# rgbstripe_fft_pcb.net
KiCad netlist of a schematic drawn in EAGLE
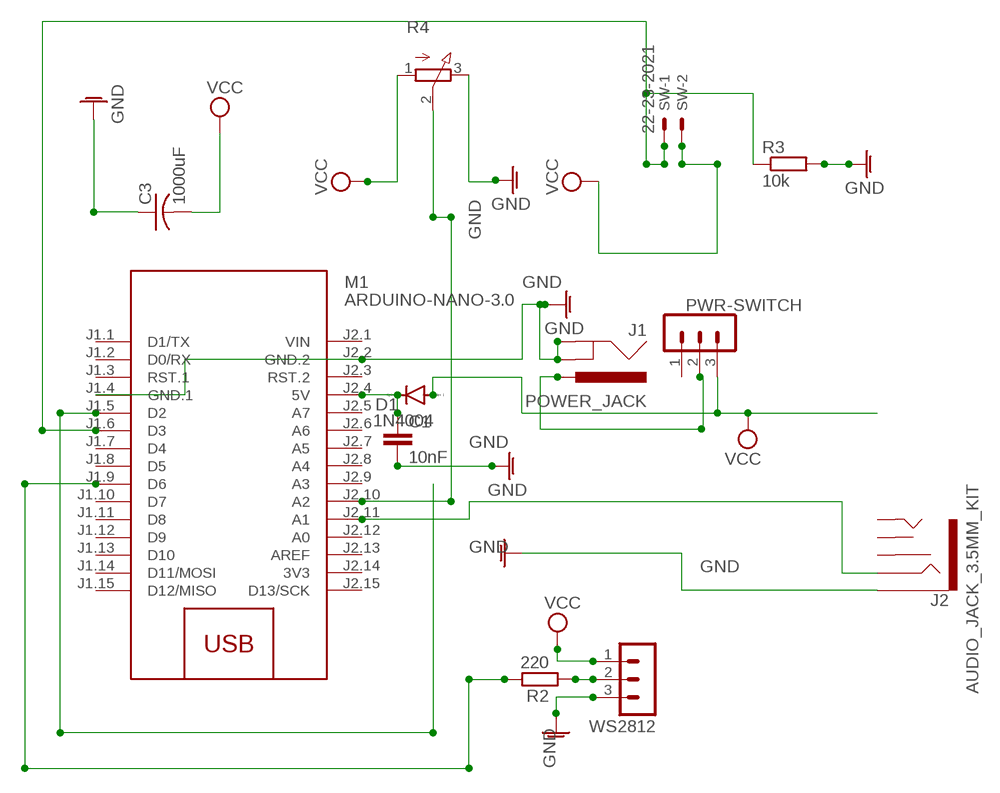
[diagram p0: schematic, sheet 1]

(export (version "E")
  (design (tool "Eeschema 10.0.6"))
  (components
    (comp (ref "C1")
      (value "10nF")
      (footprint "eagle-import:C025-025X050")
      (libsource (lib "eagle-import") (part "C-EU025-025X050"))
    )
    (comp (ref "C3")
      (value "1000uF")
      (footprint "eagle-import:C050-024X044")
      (libsource (lib "eagle-import") (part "C-US050-024X044"))
    )
    (comp (ref "D1")
      (value "1N4004")
      (footprint "eagle-import:DO41-10")
      (libsource (lib "eagle-import") (part "1N4004"))
    )
    (comp (ref "J1")
      (value "POWER_JACK")
      (footprint "eagle-import:POWER_JACK_PTH")
      (libsource (lib "eagle-import") (part "POWER_JACK"))
    )
    (comp (ref "J2")
      (value "AUDIO_JACK_3.5MM_KIT")
      (footprint "eagle-import:AUDIO-JACK-KIT")
      (libsource (lib "eagle-import") (part "AUDIO_JACK_3.5MM_KIT"))
    )
    (comp (ref "M1")
      (value "ARDUINO-NANO-3.0")
      (footprint "eagle-import:ARDUINO-NANO-3.0")
      (libsource (lib "eagle-import") (part "ARDUINO-NANO-3.0"))
    )
    (comp (ref "PWR-SWITCH")
      (value "MA03-1")
      (footprint "eagle-import:MA03-1")
      (libsource (lib "eagle-import") (part "MA03-1"))
    )
    (comp (ref "R2")
      (value "220")
      (footprint "eagle-import:0204_5")
      (libsource (lib "eagle-import") (part "R-EU_0204/5"))
    )
    (comp (ref "R3")
      (value "10k")
      (footprint "eagle-import:0204_5")
      (libsource (lib "eagle-import") (part "R-EU_0204/5"))
    )
    (comp (ref "R4")
      (value "3RP/1610N")
      (footprint "eagle-import:3RP_1610N")
      (libsource (lib "eagle-import") (part "3RP/1610N"))
    )
    (comp (ref "SW")
      (value "22-23-2021")
      (footprint "eagle-import:22-23-2021")
      (fields (field (name "MF") "MOLEX"))
      (libsource (lib "eagle-import") (part "22-23-2021"))
    )
    (comp (ref "WS2812")
      (value "MA03-1")
      (footprint "eagle-import:MA03-1")
      (libsource (lib "eagle-import") (part "MA03-1"))
    )
  )
  (nets
    (net (code "1") (name "/3V3") (class "Default")
      (node (ref "M1") (pin "J2.14") (pinfunction "3V3_J2.14") (pintype "power_in"))
    )
    (net (code "2") (name "/VIN") (class "Default")
      (node (ref "M1") (pin "J2.1") (pinfunction "VIN_J2.1") (pintype "power_in"))
    )
    (net (code "3") (name "GND") (class "Default")
      (node (ref "C1") (pin "2") (pinfunction "2_2") (pintype "passive"))
      (node (ref "C3") (pin "1") (pinfunction "1_1") (pintype "passive"))
      (node (ref "J1") (pin "GND") (pinfunction "GND_GND") (pintype "bidirectional"))
      (node (ref "J1") (pin "GNDBREAK") (pinfunction "GNDBREAK_GNDBREAK") (pintype "bidirectional"))
      (node (ref "J2") (pin "SLEEVE") (pinfunction "SLEEVE_SLEEVE") (pintype "bidirectional"))
      (node (ref "M1") (pin "J1.4") (pinfunction "GND.1_J1.4") (pintype "power_in"))
      (node (ref "M1") (pin "J2.2") (pinfunction "GND.2_J2.2") (pintype "power_in"))
      (node (ref "R3") (pin "2") (pinfunction "2_2") (pintype "passive"))
      (node (ref "R4") (pin "3") (pinfunction "E_3") (pintype "passive"))
      (node (ref "WS2812") (pin "3") (pinfunction "3_3") (pintype "passive"))
    )
    (net (code "4") (name "Net-(J1-PadPWR)") (class "Default")
      (node (ref "J1") (pin "PWR") (pinfunction "PWR_PWR") (pintype "bidirectional"))
      (node (ref "PWR-SWITCH") (pin "2") (pinfunction "2_2") (pintype "passive"))
    )
    (net (code "5") (name "Net-(M1-5V)") (class "Default")
      (node (ref "C1") (pin "1") (pinfunction "1_1") (pintype "passive"))
      (node (ref "D1") (pin "C") (pinfunction "C_C") (pintype "passive"))
      (node (ref "M1") (pin "J2.4") (pinfunction "5V_J2.4") (pintype "power_in"))
    )
    (net (code "6") (name "Net-(M1-A1)") (class "Default")
      (node (ref "J2") (pin "RING") (pinfunction "RING_RING") (pintype "bidirectional"))
      (node (ref "M1") (pin "J2.11") (pinfunction "A1_J2.11") (pintype "bidirectional"))
    )
    (net (code "7") (name "Net-(M1-A2)") (class "Default")
      (node (ref "M1") (pin "J2.10") (pinfunction "A2_J2.10") (pintype "bidirectional"))
      (node (ref "R4") (pin "2") (pinfunction "S_2") (pintype "passive"))
    )
    (net (code "8") (name "Net-(M1-D3)") (class "Default")
      (node (ref "M1") (pin "J1.6") (pinfunction "D3_J1.6") (pintype "bidirectional"))
      (node (ref "R3") (pin "1") (pinfunction "1_1") (pintype "passive"))
      (node (ref "SW") (pin "1") (pinfunction "S_1") (pintype "passive"))
    )
    (net (code "9") (name "Net-(M1-D6)") (class "Default")
      (node (ref "M1") (pin "J1.9") (pinfunction "D6_J1.9") (pintype "bidirectional"))
      (node (ref "R2") (pin "2") (pinfunction "2_2") (pintype "passive"))
    )
    (net (code "10") (name "Net-(R2-Pad1)") (class "Default")
      (node (ref "R2") (pin "1") (pinfunction "1_1") (pintype "passive"))
      (node (ref "WS2812") (pin "2") (pinfunction "2_2") (pintype "passive"))
    )
    (net (code "11") (name "VCC") (class "Default")
      (node (ref "C3") (pin "2") (pinfunction "2_2") (pintype "passive"))
      (node (ref "D1") (pin "A") (pinfunction "A_A") (pintype "passive"))
      (node (ref "PWR-SWITCH") (pin "3") (pinfunction "3_3") (pintype "passive"))
      (node (ref "R4") (pin "1") (pinfunction "A_1") (pintype "passive"))
      (node (ref "SW") (pin "2") (pinfunction "S_2") (pintype "passive"))
      (node (ref "WS2812") (pin "1") (pinfunction "1_1") (pintype "passive"))
    )
    (net (code "12") (name "unconnected-(J2-PadRSH)") (class "Default")
      (node (ref "J2") (pin "RSH") (pinfunction "RSH_RSH") (pintype "bidirectional"))
    )
    (net (code "13") (name "unconnected-(J2-PadTIP)") (class "Default")
      (node (ref "J2") (pin "TIP") (pinfunction "TIP_TIP") (pintype "bidirectional"))
    )
    (net (code "14") (name "unconnected-(J2-PadTSH)") (class "Default")
      (node (ref "J2") (pin "TSH") (pinfunction "TSH_TSH") (pintype "bidirectional"))
    )
    (net (code "15") (name "unconnected-(M1-A0-PadJ2.12)") (class "Default")
      (node (ref "M1") (pin "J2.12") (pinfunction "A0_J2.12") (pintype "bidirectional"))
    )
    (net (code "16") (name "unconnected-(M1-A3-PadJ2.9)") (class "Default")
      (node (ref "M1") (pin "J2.9") (pinfunction "A3_J2.9") (pintype "bidirectional"))
    )
    (net (code "17") (name "unconnected-(M1-A4-PadJ2.8)") (class "Default")
      (node (ref "M1") (pin "J2.8") (pinfunction "A4_J2.8") (pintype "bidirectional"))
    )
    (net (code "18") (name "unconnected-(M1-A5-PadJ2.7)") (class "Default")
      (node (ref "M1") (pin "J2.7") (pinfunction "A5_J2.7") (pintype "bidirectional"))
    )
    (net (code "19") (name "unconnected-(M1-A6-PadJ2.6)") (class "Default")
      (node (ref "M1") (pin "J2.6") (pinfunction "A6_J2.6") (pintype "bidirectional"))
    )
    (net (code "20") (name "unconnected-(M1-A7-PadJ2.5)") (class "Default")
      (node (ref "M1") (pin "J2.5") (pinfunction "A7_J2.5") (pintype "bidirectional"))
    )
    (net (code "21") (name "unconnected-(M1-AREF-PadJ2.13)") (class "Default")
      (node (ref "M1") (pin "J2.13") (pinfunction "AREF_J2.13") (pintype "bidirectional"))
    )
    (net (code "22") (name "unconnected-(M1-D0{slash}RX-PadJ1.2)") (class "Default")
      (node (ref "M1") (pin "J1.2") (pinfunction "D0/RX_J1.2") (pintype "bidirectional"))
    )
    (net (code "23") (name "unconnected-(M1-D1{slash}TX-PadJ1.1)") (class "Default")
      (node (ref "M1") (pin "J1.1") (pinfunction "D1/TX_J1.1") (pintype "bidirectional"))
    )
    (net (code "24") (name "unconnected-(M1-D2-PadJ1.5)") (class "Default")
      (node (ref "M1") (pin "J1.5") (pinfunction "D2_J1.5") (pintype "bidirectional"))
    )
    (net (code "25") (name "unconnected-(M1-D4-PadJ1.7)") (class "Default")
      (node (ref "M1") (pin "J1.7") (pinfunction "D4_J1.7") (pintype "bidirectional"))
    )
    (net (code "26") (name "unconnected-(M1-D5-PadJ1.8)") (class "Default")
      (node (ref "M1") (pin "J1.8") (pinfunction "D5_J1.8") (pintype "bidirectional"))
    )
    (net (code "27") (name "unconnected-(M1-D7-PadJ1.10)") (class "Default")
      (node (ref "M1") (pin "J1.10") (pinfunction "D7_J1.10") (pintype "bidirectional"))
    )
    (net (code "28") (name "unconnected-(M1-D8-PadJ1.11)") (class "Default")
      (node (ref "M1") (pin "J1.11") (pinfunction "D8_J1.11") (pintype "bidirectional"))
    )
    (net (code "29") (name "unconnected-(M1-D9-PadJ1.12)") (class "Default")
      (node (ref "M1") (pin "J1.12") (pinfunction "D9_J1.12") (pintype "bidirectional"))
    )
    (net (code "30") (name "unconnected-(M1-D10-PadJ1.13)") (class "Default")
      (node (ref "M1") (pin "J1.13") (pinfunction "D10_J1.13") (pintype "bidirectional"))
    )
    (net (code "31") (name "unconnected-(M1-D11{slash}MOSI-PadJ1.14)") (class "Default")
      (node (ref "M1") (pin "J1.14") (pinfunction "D11/MOSI_J1.14") (pintype "bidirectional"))
    )
    (net (code "32") (name "unconnected-(M1-D12{slash}MISO-PadJ1.15)") (class "Default")
      (node (ref "M1") (pin "J1.15") (pinfunction "D12/MISO_J1.15") (pintype "bidirectional"))
    )
    (net (code "33") (name "unconnected-(M1-D13{slash}SCK-PadJ2.15)") (class "Default")
      (node (ref "M1") (pin "J2.15") (pinfunction "D13/SCK_J2.15") (pintype "bidirectional"))
    )
    (net (code "34") (name "unconnected-(M1-RST.1-PadJ1.3)") (class "Default")
      (node (ref "M1") (pin "J1.3") (pinfunction "RST.1_J1.3") (pintype "bidirectional"))
    )
    (net (code "35") (name "unconnected-(M1-RST.2-PadJ2.3)") (class "Default")
      (node (ref "M1") (pin "J2.3") (pinfunction "RST.2_J2.3") (pintype "bidirectional"))
    )
    (net (code "36") (name "unconnected-(PWR-SWITCH-Pad1)") (class "Default")
      (node (ref "PWR-SWITCH") (pin "1") (pinfunction "1_1") (pintype "passive"))
    )
  )
)
